# W533X.net
KiCad netlist of a schematic drawn in EAGLE
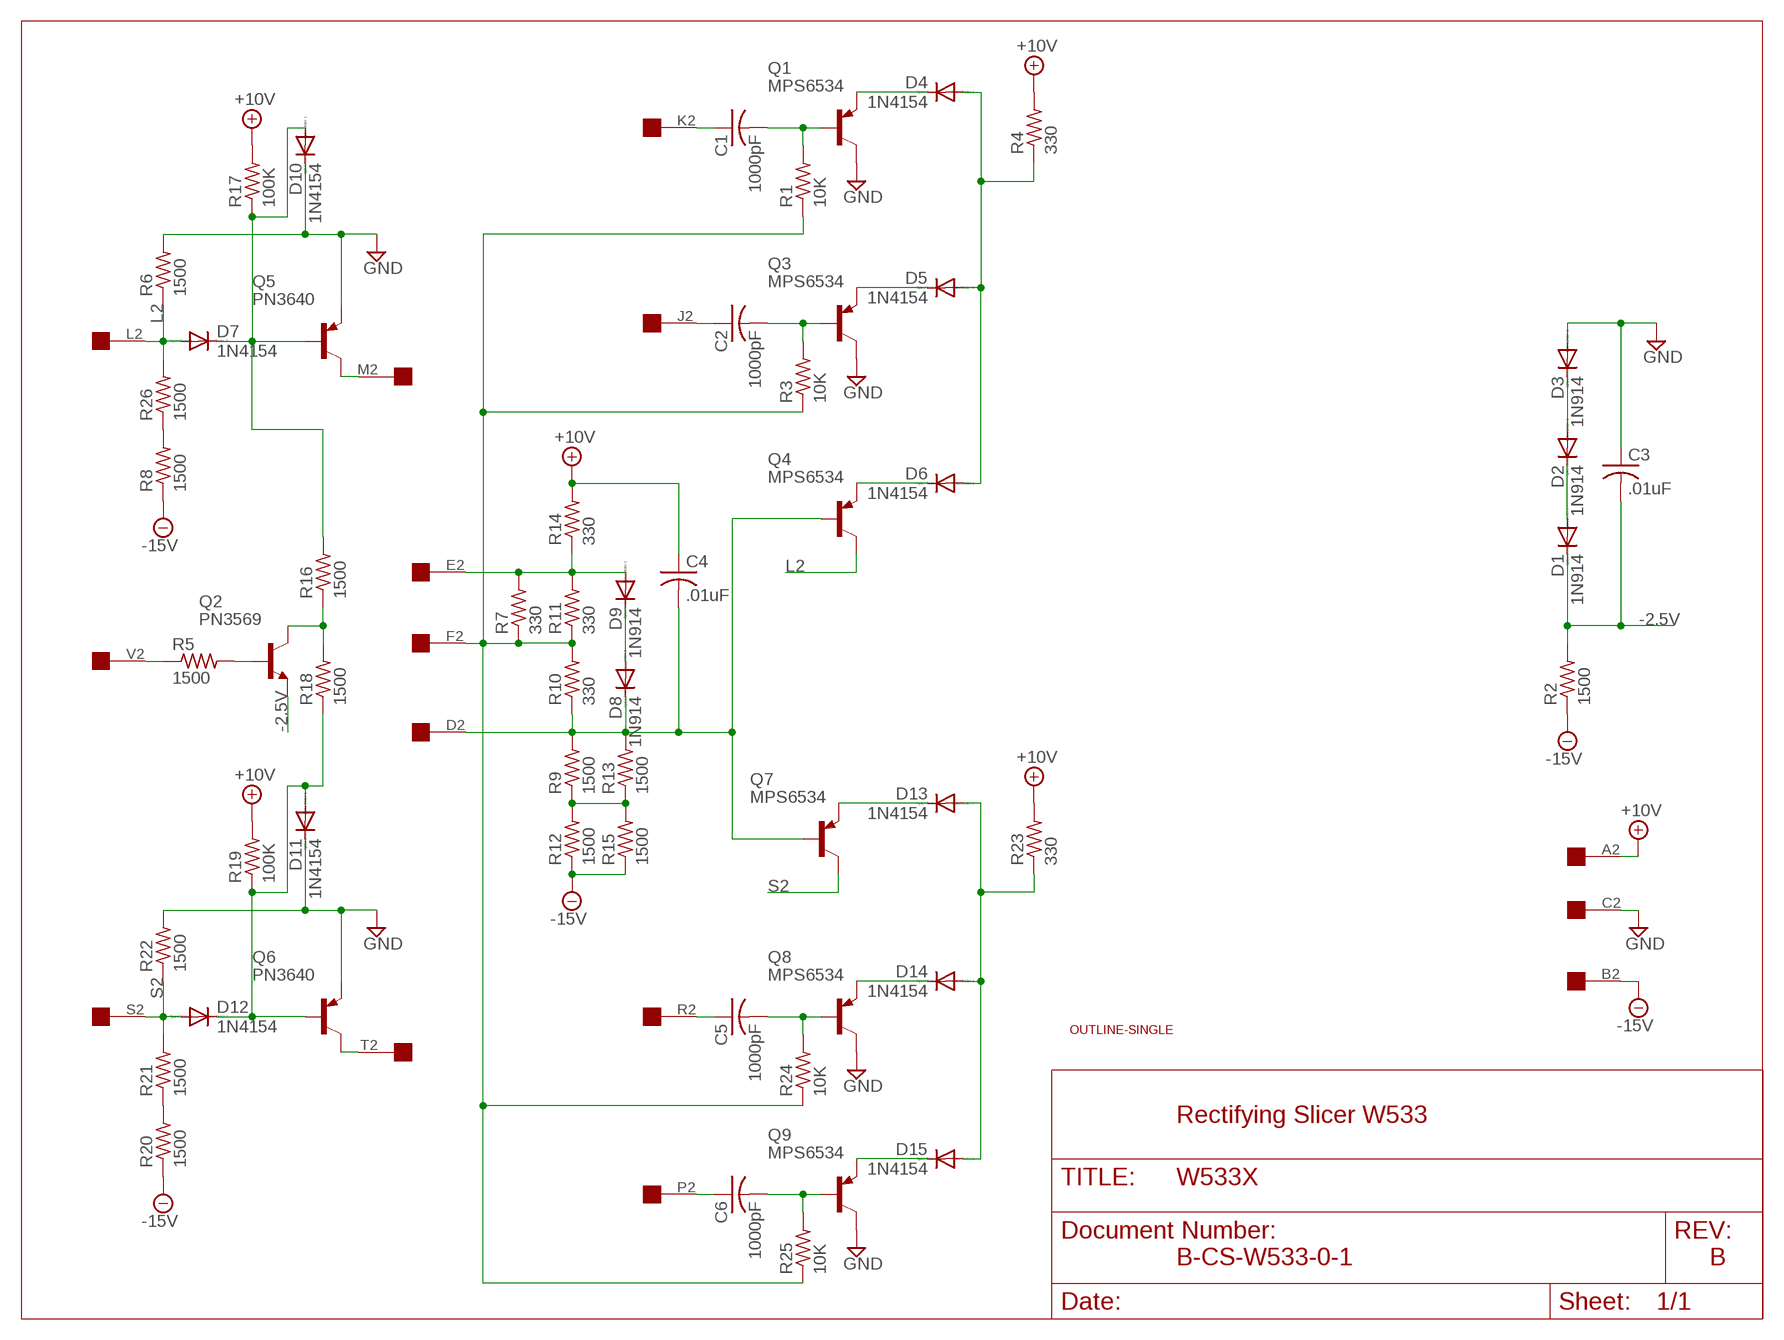
[diagram p0: schematic, sheet 1]

(export (version "E")
  (design (tool "Eeschema 10.0.6"))
  (components
    (comp (ref "C1")
      (value "1000pF")
      (footprint "eagle-import:C075-032X103")
      (libsource (lib "eagle-import") (part "C-US075-032X103"))
    )
    (comp (ref "C2")
      (value "1000pF")
      (footprint "eagle-import:C075-032X103")
      (libsource (lib "eagle-import") (part "C-US075-032X103"))
    )
    (comp (ref "C3")
      (value ".01uF")
      (footprint "eagle-import:C050-025X075")
      (libsource (lib "eagle-import") (part "C-US050-025X075"))
    )
    (comp (ref "C4")
      (value ".01uF")
      (footprint "eagle-import:C050-025X075")
      (libsource (lib "eagle-import") (part "C-US050-025X075"))
    )
    (comp (ref "C5")
      (value "1000pF")
      (footprint "eagle-import:C075-032X103")
      (libsource (lib "eagle-import") (part "C-US075-032X103"))
    )
    (comp (ref "C6")
      (value "1000pF")
      (footprint "eagle-import:C075-032X103")
      (libsource (lib "eagle-import") (part "C-US075-032X103"))
    )
    (comp (ref "D1")
      (value "1N914")
      (footprint "eagle-import:DO35-10")
      (libsource (lib "eagle-import") (part "1N4148DO35-10"))
    )
    (comp (ref "D2")
      (value "1N914")
      (footprint "eagle-import:DO35-10")
      (libsource (lib "eagle-import") (part "1N4148DO35-10"))
    )
    (comp (ref "D3")
      (value "1N914")
      (footprint "eagle-import:DO35-10")
      (libsource (lib "eagle-import") (part "1N4148DO35-10"))
    )
    (comp (ref "D4")
      (value "1N4154")
      (footprint "eagle-import:DO35-10")
      (libsource (lib "eagle-import") (part "1N4148DO35-10"))
    )
    (comp (ref "D5")
      (value "1N4154")
      (footprint "eagle-import:DO35-10")
      (libsource (lib "eagle-import") (part "1N4148DO35-10"))
    )
    (comp (ref "D6")
      (value "1N4154")
      (footprint "eagle-import:DO35-10")
      (libsource (lib "eagle-import") (part "1N4148DO35-10"))
    )
    (comp (ref "D7")
      (value "1N4154")
      (footprint "eagle-import:DO35-10")
      (libsource (lib "eagle-import") (part "1N4148DO35-10"))
    )
    (comp (ref "D8")
      (value "1N914")
      (footprint "eagle-import:DO35-10")
      (libsource (lib "eagle-import") (part "1N4148DO35-10"))
    )
    (comp (ref "D9")
      (value "1N914")
      (footprint "eagle-import:DO35-10")
      (libsource (lib "eagle-import") (part "1N4148DO35-10"))
    )
    (comp (ref "D10")
      (value "1N4154")
      (footprint "eagle-import:DO35-10")
      (libsource (lib "eagle-import") (part "1N4148DO35-10"))
    )
    (comp (ref "D11")
      (value "1N4154")
      (footprint "eagle-import:DO35-10")
      (libsource (lib "eagle-import") (part "1N4148DO35-10"))
    )
    (comp (ref "D12")
      (value "1N4154")
      (footprint "eagle-import:DO35-10")
      (libsource (lib "eagle-import") (part "1N4148DO35-10"))
    )
    (comp (ref "D13")
      (value "1N4154")
      (footprint "eagle-import:DO35-10")
      (libsource (lib "eagle-import") (part "1N4148DO35-10"))
    )
    (comp (ref "D14")
      (value "1N4154")
      (footprint "eagle-import:DO35-10")
      (libsource (lib "eagle-import") (part "1N4148DO35-10"))
    )
    (comp (ref "D15")
      (value "1N4154")
      (footprint "eagle-import:DO35-10")
      (libsource (lib "eagle-import") (part "1N4148DO35-10"))
    )
    (comp (ref "Q1")
      (value "MPS6534")
      (footprint "eagle-import:TO39")
      (libsource (lib "eagle-import") (part "2N2904"))
    )
    (comp (ref "Q2")
      (value "PN3569")
      (footprint "eagle-import:TO5")
      (libsource (lib "eagle-import") (part "2N2102"))
    )
    (comp (ref "Q3")
      (value "MPS6534")
      (footprint "eagle-import:TO39")
      (libsource (lib "eagle-import") (part "2N2904"))
    )
    (comp (ref "Q4")
      (value "MPS6534")
      (footprint "eagle-import:TO39")
      (libsource (lib "eagle-import") (part "2N2904"))
    )
    (comp (ref "Q5")
      (value "PN3640")
      (footprint "eagle-import:TO39")
      (libsource (lib "eagle-import") (part "2N2904"))
    )
    (comp (ref "Q6")
      (value "PN3640")
      (footprint "eagle-import:TO39")
      (libsource (lib "eagle-import") (part "2N2904"))
    )
    (comp (ref "Q7")
      (value "MPS6534")
      (footprint "eagle-import:TO39")
      (libsource (lib "eagle-import") (part "2N2904"))
    )
    (comp (ref "Q8")
      (value "MPS6534")
      (footprint "eagle-import:TO39")
      (libsource (lib "eagle-import") (part "2N2904"))
    )
    (comp (ref "Q9")
      (value "MPS6534")
      (footprint "eagle-import:TO39")
      (libsource (lib "eagle-import") (part "2N2904"))
    )
    (comp (ref "R1")
      (value "10K")
      (footprint "eagle-import:0207_10")
      (libsource (lib "eagle-import") (part "R-US_0207/10"))
    )
    (comp (ref "R2")
      (value "1500")
      (footprint "eagle-import:0207_10")
      (libsource (lib "eagle-import") (part "R-US_0207/10"))
    )
    (comp (ref "R3")
      (value "10K")
      (footprint "eagle-import:0207_10")
      (libsource (lib "eagle-import") (part "R-US_0207/10"))
    )
    (comp (ref "R4")
      (value "330")
      (footprint "eagle-import:0207_10")
      (libsource (lib "eagle-import") (part "R-US_0207/10"))
    )
    (comp (ref "R5")
      (value "1500")
      (footprint "eagle-import:0207_10")
      (libsource (lib "eagle-import") (part "R-US_0207/10"))
    )
    (comp (ref "R6")
      (value "1500")
      (footprint "eagle-import:0207_10")
      (libsource (lib "eagle-import") (part "R-US_0207/10"))
    )
    (comp (ref "R7")
      (value "330")
      (footprint "eagle-import:0207_10")
      (libsource (lib "eagle-import") (part "R-US_0207/10"))
    )
    (comp (ref "R8")
      (value "1500")
      (footprint "eagle-import:0207_10")
      (libsource (lib "eagle-import") (part "R-US_0207/10"))
    )
    (comp (ref "R9")
      (value "1500")
      (footprint "eagle-import:0207_10")
      (libsource (lib "eagle-import") (part "R-US_0207/10"))
    )
    (comp (ref "R10")
      (value "330")
      (footprint "eagle-import:0207_10")
      (libsource (lib "eagle-import") (part "R-US_0207/10"))
    )
    (comp (ref "R11")
      (value "330")
      (footprint "eagle-import:0207_10")
      (libsource (lib "eagle-import") (part "R-US_0207/10"))
    )
    (comp (ref "R12")
      (value "1500")
      (footprint "eagle-import:0207_10")
      (libsource (lib "eagle-import") (part "R-US_0207/10"))
    )
    (comp (ref "R13")
      (value "1500")
      (footprint "eagle-import:0207_10")
      (libsource (lib "eagle-import") (part "R-US_0207/10"))
    )
    (comp (ref "R14")
      (value "330")
      (footprint "eagle-import:0207_10")
      (libsource (lib "eagle-import") (part "R-US_0207/10"))
    )
    (comp (ref "R15")
      (value "1500")
      (footprint "eagle-import:0207_10")
      (libsource (lib "eagle-import") (part "R-US_0207/10"))
    )
    (comp (ref "R16")
      (value "1500")
      (footprint "eagle-import:0207_10")
      (libsource (lib "eagle-import") (part "R-US_0207/10"))
    )
    (comp (ref "R17")
      (value "100K")
      (footprint "eagle-import:0207_10")
      (libsource (lib "eagle-import") (part "R-US_0207/10"))
    )
    (comp (ref "R18")
      (value "1500")
      (footprint "eagle-import:0207_10")
      (libsource (lib "eagle-import") (part "R-US_0207/10"))
    )
    (comp (ref "R19")
      (value "100K")
      (footprint "eagle-import:0207_10")
      (libsource (lib "eagle-import") (part "R-US_0207/10"))
    )
    (comp (ref "R20")
      (value "1500")
      (footprint "eagle-import:0207_10")
      (libsource (lib "eagle-import") (part "R-US_0207/10"))
    )
    (comp (ref "R21")
      (value "1500")
      (footprint "eagle-import:0207_10")
      (libsource (lib "eagle-import") (part "R-US_0207/10"))
    )
    (comp (ref "R22")
      (value "1500")
      (footprint "eagle-import:0207_10")
      (libsource (lib "eagle-import") (part "R-US_0207/10"))
    )
    (comp (ref "R23")
      (value "330")
      (footprint "eagle-import:0207_10")
      (libsource (lib "eagle-import") (part "R-US_0207/10"))
    )
    (comp (ref "R24")
      (value "10K")
      (footprint "eagle-import:0207_10")
      (libsource (lib "eagle-import") (part "R-US_0207/10"))
    )
    (comp (ref "R25")
      (value "10K")
      (footprint "eagle-import:0207_10")
      (libsource (lib "eagle-import") (part "R-US_0207/10"))
    )
    (comp (ref "R26")
      (value "1500")
      (footprint "eagle-import:0207_10")
      (libsource (lib "eagle-import") (part "R-US_0207/10"))
    )
    (comp (ref "U$1")
      (value "OUTLINE-SINGLE")
      (footprint "eagle-import:SINGLE")
      (libsource (lib "eagle-import") (part "OUTLINE-SINGLE"))
    )
    (comp (ref "U$2")
      (value "EDGE-1")
      (footprint "eagle-import:EDGE-CON1")
      (libsource (lib "eagle-import") (part "EDGE-1"))
    )
  )
  (nets
    (net (code "1") (name "+10V") (class "Default")
      (node (ref "C4") (pin "1") (pinfunction "1_1") (pintype "passive"))
      (node (ref "R14") (pin "2") (pinfunction "2_2") (pintype "passive"))
      (node (ref "R17") (pin "2") (pinfunction "2_2") (pintype "passive"))
      (node (ref "R19") (pin "2") (pinfunction "2_2") (pintype "passive"))
      (node (ref "R23") (pin "2") (pinfunction "2_2") (pintype "passive"))
      (node (ref "R4") (pin "2") (pinfunction "2_2") (pintype "passive"))
      (node (ref "U$2") (pin "A2") (pinfunction "1_A2") (pintype "bidirectional"))
    )
    (net (code "2") (name "-15V") (class "Default")
      (node (ref "R12") (pin "1") (pinfunction "1_1") (pintype "passive"))
      (node (ref "R15") (pin "1") (pinfunction "1_1") (pintype "passive"))
      (node (ref "R2") (pin "1") (pinfunction "1_1") (pintype "passive"))
      (node (ref "R20") (pin "1") (pinfunction "1_1") (pintype "passive"))
      (node (ref "R8") (pin "1") (pinfunction "1_1") (pintype "passive"))
      (node (ref "U$2") (pin "B2") (pinfunction "1_B2") (pintype "bidirectional"))
    )
    (net (code "3") (name "/-2.5V") (class "Default")
      (node (ref "C3") (pin "2") (pinfunction "2_2") (pintype "passive"))
      (node (ref "D1") (pin "C") (pinfunction "C_C") (pintype "passive"))
      (node (ref "Q2") (pin "1") (pinfunction "E_1") (pintype "passive"))
      (node (ref "R2") (pin "2") (pinfunction "2_2") (pintype "passive"))
    )
    (net (code "4") (name "/L2") (class "Default")
      (node (ref "D7") (pin "A") (pinfunction "A_A") (pintype "passive"))
      (node (ref "Q4") (pin "3") (pinfunction "C_3") (pintype "passive"))
      (node (ref "R26") (pin "2") (pinfunction "2_2") (pintype "passive"))
      (node (ref "R6") (pin "1") (pinfunction "1_1") (pintype "passive"))
      (node (ref "U$2") (pin "L2") (pinfunction "1_L2") (pintype "bidirectional"))
    )
    (net (code "5") (name "/S2") (class "Default")
      (node (ref "D12") (pin "A") (pinfunction "A_A") (pintype "passive"))
      (node (ref "Q7") (pin "3") (pinfunction "C_3") (pintype "passive"))
      (node (ref "R21") (pin "2") (pinfunction "2_2") (pintype "passive"))
      (node (ref "R22") (pin "1") (pinfunction "1_1") (pintype "passive"))
      (node (ref "U$2") (pin "S2") (pinfunction "1_S2") (pintype "bidirectional"))
    )
    (net (code "6") (name "GND") (class "Default")
      (node (ref "C3") (pin "1") (pinfunction "1_1") (pintype "passive"))
      (node (ref "D10") (pin "C") (pinfunction "C_C") (pintype "passive"))
      (node (ref "D11") (pin "C") (pinfunction "C_C") (pintype "passive"))
      (node (ref "D3") (pin "A") (pinfunction "A_A") (pintype "passive"))
      (node (ref "Q1") (pin "3") (pinfunction "C_3") (pintype "passive"))
      (node (ref "Q3") (pin "3") (pinfunction "C_3") (pintype "passive"))
      (node (ref "Q5") (pin "1") (pinfunction "E_1") (pintype "passive"))
      (node (ref "Q6") (pin "1") (pinfunction "E_1") (pintype "passive"))
      (node (ref "Q8") (pin "3") (pinfunction "C_3") (pintype "passive"))
      (node (ref "Q9") (pin "3") (pinfunction "C_3") (pintype "passive"))
      (node (ref "R22") (pin "2") (pinfunction "2_2") (pintype "passive"))
      (node (ref "R6") (pin "2") (pinfunction "2_2") (pintype "passive"))
      (node (ref "U$2") (pin "C2") (pinfunction "1_C2") (pintype "bidirectional"))
    )
    (net (code "7") (name "Net-(D1-PadA)") (class "Default")
      (node (ref "D1") (pin "A") (pinfunction "A_A") (pintype "passive"))
      (node (ref "D2") (pin "C") (pinfunction "C_C") (pintype "passive"))
    )
    (net (code "8") (name "Net-(D2-PadA)") (class "Default")
      (node (ref "D2") (pin "A") (pinfunction "A_A") (pintype "passive"))
      (node (ref "D3") (pin "C") (pinfunction "C_C") (pintype "passive"))
    )
    (net (code "9") (name "Net-(D4-PadA)") (class "Default")
      (node (ref "D4") (pin "A") (pinfunction "A_A") (pintype "passive"))
      (node (ref "D5") (pin "A") (pinfunction "A_A") (pintype "passive"))
      (node (ref "D6") (pin "A") (pinfunction "A_A") (pintype "passive"))
      (node (ref "R4") (pin "1") (pinfunction "1_1") (pintype "passive"))
    )
    (net (code "10") (name "Net-(D8-PadA)") (class "Default")
      (node (ref "D8") (pin "A") (pinfunction "A_A") (pintype "passive"))
      (node (ref "D9") (pin "C") (pinfunction "C_C") (pintype "passive"))
    )
    (net (code "11") (name "Net-(D13-PadA)") (class "Default")
      (node (ref "D13") (pin "A") (pinfunction "A_A") (pintype "passive"))
      (node (ref "D14") (pin "A") (pinfunction "A_A") (pintype "passive"))
      (node (ref "D15") (pin "A") (pinfunction "A_A") (pintype "passive"))
      (node (ref "R23") (pin "1") (pinfunction "1_1") (pintype "passive"))
    )
    (net (code "12") (name "Net-(Q1-B)") (class "Default")
      (node (ref "C1") (pin "2") (pinfunction "2_2") (pintype "passive"))
      (node (ref "Q1") (pin "2") (pinfunction "B_2") (pintype "passive"))
      (node (ref "R1") (pin "2") (pinfunction "2_2") (pintype "passive"))
    )
    (net (code "13") (name "Net-(Q1-E)") (class "Default")
      (node (ref "D4") (pin "C") (pinfunction "C_C") (pintype "passive"))
      (node (ref "Q1") (pin "1") (pinfunction "E_1") (pintype "passive"))
    )
    (net (code "14") (name "Net-(Q2-B)") (class "Default")
      (node (ref "Q2") (pin "2") (pinfunction "B_2") (pintype "passive"))
      (node (ref "R5") (pin "2") (pinfunction "2_2") (pintype "passive"))
    )
    (net (code "15") (name "Net-(Q2-C)") (class "Default")
      (node (ref "Q2") (pin "3") (pinfunction "C_3") (pintype "passive"))
      (node (ref "R16") (pin "1") (pinfunction "1_1") (pintype "passive"))
      (node (ref "R18") (pin "2") (pinfunction "2_2") (pintype "passive"))
    )
    (net (code "16") (name "Net-(Q3-B)") (class "Default")
      (node (ref "C2") (pin "2") (pinfunction "2_2") (pintype "passive"))
      (node (ref "Q3") (pin "2") (pinfunction "B_2") (pintype "passive"))
      (node (ref "R3") (pin "2") (pinfunction "2_2") (pintype "passive"))
    )
    (net (code "17") (name "Net-(Q3-E)") (class "Default")
      (node (ref "D5") (pin "C") (pinfunction "C_C") (pintype "passive"))
      (node (ref "Q3") (pin "1") (pinfunction "E_1") (pintype "passive"))
    )
    (net (code "18") (name "Net-(Q4-B)") (class "Default")
      (node (ref "C4") (pin "2") (pinfunction "2_2") (pintype "passive"))
      (node (ref "D8") (pin "C") (pinfunction "C_C") (pintype "passive"))
      (node (ref "Q4") (pin "2") (pinfunction "B_2") (pintype "passive"))
      (node (ref "Q7") (pin "2") (pinfunction "B_2") (pintype "passive"))
      (node (ref "R10") (pin "1") (pinfunction "1_1") (pintype "passive"))
      (node (ref "R13") (pin "2") (pinfunction "2_2") (pintype "passive"))
      (node (ref "R9") (pin "2") (pinfunction "2_2") (pintype "passive"))
      (node (ref "U$2") (pin "D2") (pinfunction "1_D2") (pintype "bidirectional"))
    )
    (net (code "19") (name "Net-(Q4-E)") (class "Default")
      (node (ref "D6") (pin "C") (pinfunction "C_C") (pintype "passive"))
      (node (ref "Q4") (pin "1") (pinfunction "E_1") (pintype "passive"))
    )
    (net (code "20") (name "Net-(Q5-B)") (class "Default")
      (node (ref "D10") (pin "A") (pinfunction "A_A") (pintype "passive"))
      (node (ref "D7") (pin "C") (pinfunction "C_C") (pintype "passive"))
      (node (ref "Q5") (pin "2") (pinfunction "B_2") (pintype "passive"))
      (node (ref "R16") (pin "2") (pinfunction "2_2") (pintype "passive"))
      (node (ref "R17") (pin "1") (pinfunction "1_1") (pintype "passive"))
    )
    (net (code "21") (name "Net-(Q5-C)") (class "Default")
      (node (ref "Q5") (pin "3") (pinfunction "C_3") (pintype "passive"))
      (node (ref "U$2") (pin "M2") (pinfunction "1_M2") (pintype "bidirectional"))
    )
    (net (code "22") (name "Net-(Q6-B)") (class "Default")
      (node (ref "D11") (pin "A") (pinfunction "A_A") (pintype "passive"))
      (node (ref "D12") (pin "C") (pinfunction "C_C") (pintype "passive"))
      (node (ref "Q6") (pin "2") (pinfunction "B_2") (pintype "passive"))
      (node (ref "R18") (pin "1") (pinfunction "1_1") (pintype "passive"))
      (node (ref "R19") (pin "1") (pinfunction "1_1") (pintype "passive"))
    )
    (net (code "23") (name "Net-(Q6-C)") (class "Default")
      (node (ref "Q6") (pin "3") (pinfunction "C_3") (pintype "passive"))
      (node (ref "U$2") (pin "T2") (pinfunction "1_T2") (pintype "bidirectional"))
    )
    (net (code "24") (name "Net-(Q7-E)") (class "Default")
      (node (ref "D13") (pin "C") (pinfunction "C_C") (pintype "passive"))
      (node (ref "Q7") (pin "1") (pinfunction "E_1") (pintype "passive"))
    )
    (net (code "25") (name "Net-(Q8-B)") (class "Default")
      (node (ref "C5") (pin "2") (pinfunction "2_2") (pintype "passive"))
      (node (ref "Q8") (pin "2") (pinfunction "B_2") (pintype "passive"))
      (node (ref "R24") (pin "2") (pinfunction "2_2") (pintype "passive"))
    )
    (net (code "26") (name "Net-(Q8-E)") (class "Default")
      (node (ref "D14") (pin "C") (pinfunction "C_C") (pintype "passive"))
      (node (ref "Q8") (pin "1") (pinfunction "E_1") (pintype "passive"))
    )
    (net (code "27") (name "Net-(Q9-B)") (class "Default")
      (node (ref "C6") (pin "2") (pinfunction "2_2") (pintype "passive"))
      (node (ref "Q9") (pin "2") (pinfunction "B_2") (pintype "passive"))
      (node (ref "R25") (pin "2") (pinfunction "2_2") (pintype "passive"))
    )
    (net (code "28") (name "Net-(Q9-E)") (class "Default")
      (node (ref "D15") (pin "C") (pinfunction "C_C") (pintype "passive"))
      (node (ref "Q9") (pin "1") (pinfunction "E_1") (pintype "passive"))
    )
    (net (code "29") (name "Net-(R12-Pad2)") (class "Default")
      (node (ref "R12") (pin "2") (pinfunction "2_2") (pintype "passive"))
      (node (ref "R13") (pin "1") (pinfunction "1_1") (pintype "passive"))
      (node (ref "R15") (pin "2") (pinfunction "2_2") (pintype "passive"))
      (node (ref "R9") (pin "1") (pinfunction "1_1") (pintype "passive"))
    )
    (net (code "30") (name "Net-(R20-Pad2)") (class "Default")
      (node (ref "R20") (pin "2") (pinfunction "2_2") (pintype "passive"))
      (node (ref "R21") (pin "1") (pinfunction "1_1") (pintype "passive"))
    )
    (net (code "31") (name "Net-(R26-Pad1)") (class "Default")
      (node (ref "R26") (pin "1") (pinfunction "1_1") (pintype "passive"))
      (node (ref "R8") (pin "2") (pinfunction "2_2") (pintype "passive"))
    )
    (net (code "32") (name "Net-(U$2E-1)") (class "Default")
      (node (ref "D9") (pin "A") (pinfunction "A_A") (pintype "passive"))
      (node (ref "R11") (pin "2") (pinfunction "2_2") (pintype "passive"))
      (node (ref "R14") (pin "1") (pinfunction "1_1") (pintype "passive"))
      (node (ref "R7") (pin "2") (pinfunction "2_2") (pintype "passive"))
      (node (ref "U$2") (pin "E2") (pinfunction "1_E2") (pintype "bidirectional"))
    )
    (net (code "33") (name "Net-(U$2F-1)") (class "Default")
      (node (ref "R1") (pin "1") (pinfunction "1_1") (pintype "passive"))
      (node (ref "R10") (pin "2") (pinfunction "2_2") (pintype "passive"))
      (node (ref "R11") (pin "1") (pinfunction "1_1") (pintype "passive"))
      (node (ref "R24") (pin "1") (pinfunction "1_1") (pintype "passive"))
      (node (ref "R25") (pin "1") (pinfunction "1_1") (pintype "passive"))
      (node (ref "R3") (pin "1") (pinfunction "1_1") (pintype "passive"))
      (node (ref "R7") (pin "1") (pinfunction "1_1") (pintype "passive"))
      (node (ref "U$2") (pin "F2") (pinfunction "1_F2") (pintype "bidirectional"))
    )
    (net (code "34") (name "Net-(U$2H-1)") (class "Default")
      (node (ref "C2") (pin "1") (pinfunction "1_1") (pintype "passive"))
      (node (ref "U$2") (pin "J2") (pinfunction "1_J2") (pintype "bidirectional"))
    )
    (net (code "35") (name "Net-(U$2I-1)") (class "Default")
      (node (ref "C1") (pin "1") (pinfunction "1_1") (pintype "passive"))
      (node (ref "U$2") (pin "K2") (pinfunction "1_K2") (pintype "bidirectional"))
    )
    (net (code "36") (name "Net-(U$2M-1)") (class "Default")
      (node (ref "C6") (pin "1") (pinfunction "1_1") (pintype "passive"))
      (node (ref "U$2") (pin "P2") (pinfunction "1_P2") (pintype "bidirectional"))
    )
    (net (code "37") (name "Net-(U$2N-1)") (class "Default")
      (node (ref "C5") (pin "1") (pinfunction "1_1") (pintype "passive"))
      (node (ref "U$2") (pin "R2") (pinfunction "1_R2") (pintype "bidirectional"))
    )
    (net (code "38") (name "Net-(U$2R-1)") (class "Default")
      (node (ref "R5") (pin "1") (pinfunction "1_1") (pintype "passive"))
      (node (ref "U$2") (pin "V2") (pinfunction "1_V2") (pintype "bidirectional"))
    )
  )
)
